# Output_schematic.net
KiCad netlist of a schematic drawn in Altium Designer
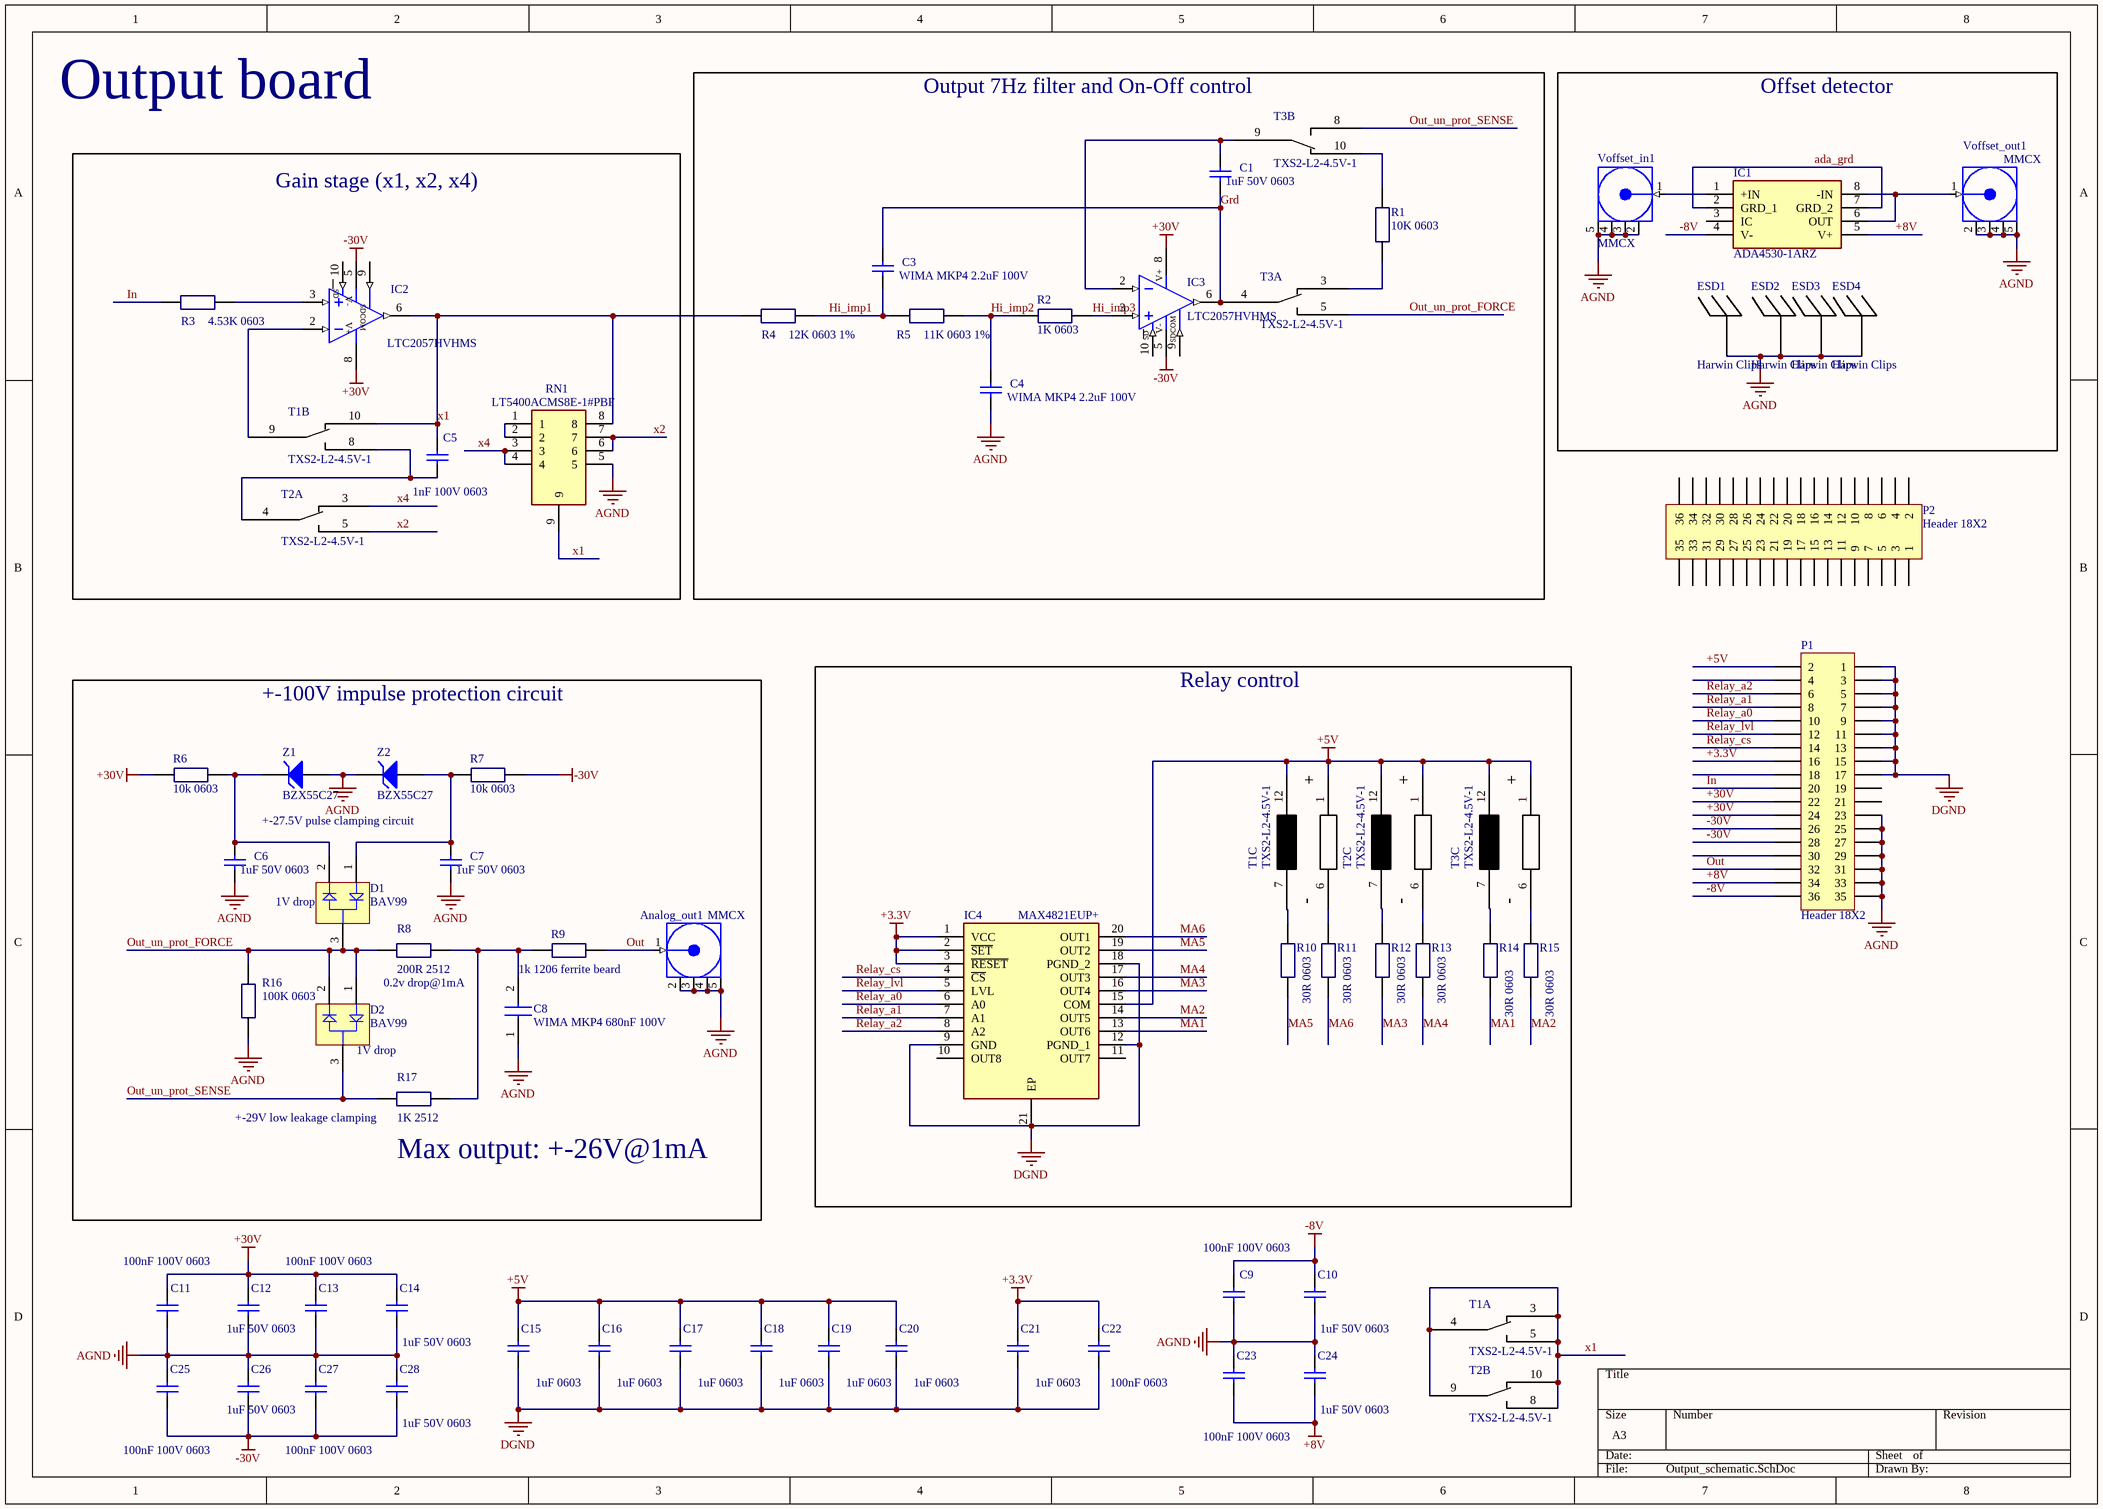
[diagram p0: Output_schematic.SchDoc]

(export (version "E")
  (design (tool "Eeschema 10.0.6"))
  (components
    (comp (ref "Analog_out1")
      (value "MMCX")
      (footprint "MMCX2.54-V5")
      (description "RF Coaxial PCB Connector, MMCX; Thru-Hole, Vertical Mount Plug,  50 Ohm Impedance")
      (fields (field (name "PUBLISHER") "Altium Limited"))
      (libsource (lib "Miscellaneous Connectors") (part "COAX-M"))
    )
    (comp (ref "C1")
      (value "1uF 50V 0603")
      (footprint "CAP 0603")
      (description "Non-polarised capacitor")
      (fields
        (field (name "PART NUMBER") "CC1206_1UF_25V_10%_X7R")
        (field (name "VOLTAGE") "25V")
        (field (name "AUTHOR") "CERN DEM JLC")
      )
      (libsource (lib "Capacitors") (part "Capacitor - non polarized"))
    )
    (comp (ref "C3")
      (value "WIMA MKP4 2.2uF 100V")
      (footprint "90g WIMA MKP4 2.2uF 100V")
      (description "Non-polarised capacitor")
      (fields
        (field (name "PART NUMBER") "CC1206_1UF_25V_10%_X7R")
        (field (name "VOLTAGE") "25V")
        (field (name "AUTHOR") "CERN DEM JLC")
      )
      (libsource (lib "Capacitors") (part "Capacitor - non polarized"))
    )
    (comp (ref "C4")
      (value "WIMA MKP4 2.2uF 100V")
      (footprint "90g WIMA MKP4 2.2uF 100V")
      (description "Non-polarised capacitor")
      (fields
        (field (name "PART NUMBER") "CC1206_1UF_25V_10%_X7R")
        (field (name "VOLTAGE") "25V")
        (field (name "AUTHOR") "CERN DEM JLC")
      )
      (libsource (lib "Capacitors") (part "Capacitor - non polarized"))
    )
    (comp (ref "C5")
      (value "1nF 100V 0603")
      (footprint "CAP 0603")
      (description "Non-polarised capacitor")
      (fields
        (field (name "PART NUMBER") "CC1206_1UF_25V_10%_X7R")
        (field (name "VOLTAGE") "25V")
        (field (name "AUTHOR") "CERN DEM JLC")
      )
      (libsource (lib "Capacitors") (part "Capacitor - non polarized"))
    )
    (comp (ref "C6")
      (value "1uF 50V 0603")
      (footprint "CAP 0603")
      (description "Non-polarised capacitor")
      (fields
        (field (name "PART NUMBER") "CC1206_1UF_25V_10%_X7R")
        (field (name "VOLTAGE") "25V")
        (field (name "AUTHOR") "CERN DEM JLC")
      )
      (libsource (lib "Capacitors") (part "Capacitor - non polarized"))
    )
    (comp (ref "C7")
      (value "1uF 50V 0603")
      (footprint "CAP 0603")
      (description "Non-polarised capacitor")
      (fields
        (field (name "PART NUMBER") "CC1206_1UF_25V_10%_X7R")
        (field (name "VOLTAGE") "25V")
        (field (name "AUTHOR") "CERN DEM JLC")
      )
      (libsource (lib "Capacitors") (part "Capacitor - non polarized"))
    )
    (comp (ref "C8")
      (value "WIMA MKP4 680nF 100V")
      (footprint "SamacSys:MKP4F036804F00KSSD")
      (description "Capacitor")
      (fields
        (field (name "MANUFACTURER_PART_NUMBER") "MKP4F036804F00KSSD")
        (field (name "MOUSER PART NUMBER") "505-MKP4F036804F00KS")
      )
      (libsource (lib "SamacSys") (part "MKP4F036804F00KSSD"))
    )
    (comp (ref "C9")
      (value "100nF 100V 0603")
      (footprint "CAP 0603")
      (description "Non-polarised capacitor")
      (fields
        (field (name "PART NUMBER") "CC1206_1UF_25V_10%_X7R")
        (field (name "VOLTAGE") "25V")
        (field (name "AUTHOR") "CERN DEM JLC")
      )
      (libsource (lib "Capacitors") (part "Capacitor - non polarized"))
    )
    (comp (ref "C10")
      (value "1uF 50V 0603")
      (footprint "CAP 0603")
      (description "Non-polarised capacitor")
      (fields
        (field (name "PART NUMBER") "CC1206_1UF_25V_10%_X7R")
        (field (name "VOLTAGE") "25V")
        (field (name "AUTHOR") "CERN DEM JLC")
      )
      (libsource (lib "Capacitors") (part "Capacitor - non polarized"))
    )
    (comp (ref "C11")
      (value "100nF 100V 0603")
      (footprint "CAP 0603")
      (description "Non-polarised capacitor")
      (fields
        (field (name "PART NUMBER") "CC1206_1UF_25V_10%_X7R")
        (field (name "VOLTAGE") "25V")
        (field (name "AUTHOR") "CERN DEM JLC")
      )
      (libsource (lib "Capacitors") (part "Capacitor - non polarized"))
    )
    (comp (ref "C12")
      (value "1uF 50V 0603")
      (footprint "CAP 0603")
      (description "Non-polarised capacitor")
      (fields
        (field (name "PART NUMBER") "CC1206_1UF_25V_10%_X7R")
        (field (name "VOLTAGE") "25V")
        (field (name "AUTHOR") "CERN DEM JLC")
      )
      (libsource (lib "Capacitors") (part "Capacitor - non polarized"))
    )
    (comp (ref "C13")
      (value "100nF 100V 0603")
      (footprint "CAP 0603")
      (description "Non-polarised capacitor")
      (fields
        (field (name "PART NUMBER") "CC1206_1UF_25V_10%_X7R")
        (field (name "VOLTAGE") "25V")
        (field (name "AUTHOR") "CERN DEM JLC")
      )
      (libsource (lib "Capacitors") (part "Capacitor - non polarized"))
    )
    (comp (ref "C14")
      (value "1uF 50V 0603")
      (footprint "CAP 0603")
      (description "Non-polarised capacitor")
      (fields
        (field (name "PART NUMBER") "CC1206_1UF_25V_10%_X7R")
        (field (name "VOLTAGE") "25V")
        (field (name "AUTHOR") "CERN DEM JLC")
      )
      (libsource (lib "Capacitors") (part "Capacitor - non polarized"))
    )
    (comp (ref "C15")
      (value "1uF 0603")
      (footprint "CAP 0603")
      (description "Non-polarised capacitor")
      (fields
        (field (name "PART NUMBER") "CC1206_1UF_25V_10%_X7R")
        (field (name "VOLTAGE") "25V")
        (field (name "AUTHOR") "CERN DEM JLC")
      )
      (libsource (lib "Capacitors") (part "Capacitor - non polarized"))
    )
    (comp (ref "C16")
      (value "1uF 0603")
      (footprint "CAP 0603")
      (description "Non-polarised capacitor")
      (fields
        (field (name "PART NUMBER") "CC1206_1UF_25V_10%_X7R")
        (field (name "VOLTAGE") "25V")
        (field (name "AUTHOR") "CERN DEM JLC")
      )
      (libsource (lib "Capacitors") (part "Capacitor - non polarized"))
    )
    (comp (ref "C17")
      (value "1uF 0603")
      (footprint "CAP 0603")
      (description "Non-polarised capacitor")
      (fields
        (field (name "PART NUMBER") "CC1206_1UF_25V_10%_X7R")
        (field (name "VOLTAGE") "25V")
        (field (name "AUTHOR") "CERN DEM JLC")
      )
      (libsource (lib "Capacitors") (part "Capacitor - non polarized"))
    )
    (comp (ref "C18")
      (value "1uF 0603")
      (footprint "CAP 0603")
      (description "Non-polarised capacitor")
      (fields
        (field (name "PART NUMBER") "CC1206_1UF_25V_10%_X7R")
        (field (name "VOLTAGE") "25V")
        (field (name "AUTHOR") "CERN DEM JLC")
      )
      (libsource (lib "Capacitors") (part "Capacitor - non polarized"))
    )
    (comp (ref "C19")
      (value "1uF 0603")
      (footprint "CAP 0603")
      (description "Non-polarised capacitor")
      (fields
        (field (name "PART NUMBER") "CC1206_1UF_25V_10%_X7R")
        (field (name "VOLTAGE") "25V")
        (field (name "AUTHOR") "CERN DEM JLC")
      )
      (libsource (lib "Capacitors") (part "Capacitor - non polarized"))
    )
    (comp (ref "C20")
      (value "1uF 0603")
      (footprint "CAP 0603")
      (description "Non-polarised capacitor")
      (fields
        (field (name "PART NUMBER") "CC1206_1UF_25V_10%_X7R")
        (field (name "VOLTAGE") "25V")
        (field (name "AUTHOR") "CERN DEM JLC")
      )
      (libsource (lib "Capacitors") (part "Capacitor - non polarized"))
    )
    (comp (ref "C21")
      (value "1uF 0603")
      (footprint "CAP 0603")
      (description "Non-polarised capacitor")
      (fields
        (field (name "PART NUMBER") "CC1206_1UF_25V_10%_X7R")
        (field (name "VOLTAGE") "25V")
        (field (name "AUTHOR") "CERN DEM JLC")
      )
      (libsource (lib "Capacitors") (part "Capacitor - non polarized"))
    )
    (comp (ref "C22")
      (value "100nF 0603")
      (footprint "CAP 0603")
      (description "Non-polarised capacitor")
      (fields
        (field (name "PART NUMBER") "CC1206_1UF_25V_10%_X7R")
        (field (name "VOLTAGE") "25V")
        (field (name "AUTHOR") "CERN DEM JLC")
      )
      (libsource (lib "Capacitors") (part "Capacitor - non polarized"))
    )
    (comp (ref "C23")
      (value "100nF 100V 0603")
      (footprint "CAP 0603")
      (description "Non-polarised capacitor")
      (fields
        (field (name "PART NUMBER") "CC1206_1UF_25V_10%_X7R")
        (field (name "VOLTAGE") "25V")
        (field (name "AUTHOR") "CERN DEM JLC")
      )
      (libsource (lib "Capacitors") (part "Capacitor - non polarized"))
    )
    (comp (ref "C24")
      (value "1uF 50V 0603")
      (footprint "CAP 0603")
      (description "Non-polarised capacitor")
      (fields
        (field (name "PART NUMBER") "CC1206_1UF_25V_10%_X7R")
        (field (name "VOLTAGE") "25V")
        (field (name "AUTHOR") "CERN DEM JLC")
      )
      (libsource (lib "Capacitors") (part "Capacitor - non polarized"))
    )
    (comp (ref "C25")
      (value "100nF 100V 0603")
      (footprint "CAP 0603")
      (description "Non-polarised capacitor")
      (fields
        (field (name "PART NUMBER") "CC1206_1UF_25V_10%_X7R")
        (field (name "VOLTAGE") "25V")
        (field (name "AUTHOR") "CERN DEM JLC")
      )
      (libsource (lib "Capacitors") (part "Capacitor - non polarized"))
    )
    (comp (ref "C26")
      (value "1uF 50V 0603")
      (footprint "CAP 0603")
      (description "Non-polarised capacitor")
      (fields
        (field (name "PART NUMBER") "CC1206_1UF_25V_10%_X7R")
        (field (name "VOLTAGE") "25V")
        (field (name "AUTHOR") "CERN DEM JLC")
      )
      (libsource (lib "Capacitors") (part "Capacitor - non polarized"))
    )
    (comp (ref "C27")
      (value "100nF 100V 0603")
      (footprint "CAP 0603")
      (description "Non-polarised capacitor")
      (fields
        (field (name "PART NUMBER") "CC1206_1UF_25V_10%_X7R")
        (field (name "VOLTAGE") "25V")
        (field (name "AUTHOR") "CERN DEM JLC")
      )
      (libsource (lib "Capacitors") (part "Capacitor - non polarized"))
    )
    (comp (ref "C28")
      (value "1uF 50V 0603")
      (footprint "CAP 0603")
      (description "Non-polarised capacitor")
      (fields
        (field (name "PART NUMBER") "CC1206_1UF_25V_10%_X7R")
        (field (name "VOLTAGE") "25V")
        (field (name "AUTHOR") "CERN DEM JLC")
      )
      (libsource (lib "Capacitors") (part "Capacitor - non polarized"))
    )
    (comp (ref "D1")
      (value "BAV99")
      (footprint "INF-SOT23_N")
      (description "Silicon Switching Diode, SOT23, Reel, Green")
      (fields (field (name "MANUFACTURER") "Infineon"))
      (libsource (lib "Infineon_Transistor_&_Diode") (part "BAV99"))
    )
    (comp (ref "D2")
      (value "BAV99")
      (footprint "INF-SOT23_N")
      (description "Silicon Switching Diode, SOT23, Reel, Green")
      (fields (field (name "MANUFACTURER") "Infineon"))
      (libsource (lib "Infineon_Transistor_&_Diode") (part "BAV99"))
    )
    (comp (ref "ESD1")
      (value "Harwin Clips")
      (footprint "HARWIN - S0981-46R - CLIP")
      (libsource (lib "My SCH library") (part "Harwin Clips"))
    )
    (comp (ref "ESD2")
      (value "Harwin Clips")
      (footprint "HARWIN - S0981-46R - CLIP")
      (libsource (lib "My SCH library") (part "Harwin Clips"))
    )
    (comp (ref "ESD3")
      (value "Harwin Clips")
      (footprint "HARWIN - S0981-46R - CLIP")
      (libsource (lib "My SCH library") (part "Harwin Clips"))
    )
    (comp (ref "ESD4")
      (value "Harwin Clips")
      (footprint "HARWIN - S0981-46R - CLIP")
      (libsource (lib "My SCH library") (part "Harwin Clips"))
    )
    (comp (ref "IC1")
      (value "ADA4530-1ARZ")
      (footprint "SamacSys:SOIC127P600X175-8N")
      (description "Integrated Circuit")
      (fields (field (name "MOUSER PART NUMBER") "584-ADA4530-1ARZ"))
      (libsource (lib "*") (part "ADA4530-1ARZ"))
    )
    (comp (ref "IC2")
      (value "LTC2057HVHMS")
      (footprint "LT-MS-10_M")
      (description "High Voltage, Low Noise, Zero-Drift Operational  Amplifier")
      (libsource (lib "Operational Amplifiers") (part "LTC2057xHMS"))
    )
    (comp (ref "IC3")
      (value "LTC2057HVHMS")
      (footprint "LT-MS-10_M")
      (description "High Voltage, Low Noise, Zero-Drift Operational  Amplifier")
      (libsource (lib "Operational Amplifiers") (part "LTC2057xHMS"))
    )
    (comp (ref "IC4")
      (value "MAX4821EUP+")
      (footprint "SamacSys:SOP65P638X110-21N")
      (description "Integrated Circuit")
      (fields (field (name "MOUSER PART NUMBER") "700-MAX4821EUP"))
      (libsource (lib "*") (part "MAX4821EUP+"))
    )
    (comp (ref "P1")
      (value "Header 18X2")
      (footprint "HDR2X18")
      (description "Header, 18-Pin, Dual row")
      (fields (field (name "PUBLISHER") "Altium Limited"))
      (libsource (lib "Miscellaneous Connectors") (part "Header 18X2"))
    )
    (comp (ref "P2")
      (value "Header 18X2")
      (footprint "HDR2X18")
      (description "Header, 18-Pin, Dual row")
      (fields (field (name "PUBLISHER") "Altium Limited"))
      (libsource (lib "") (part "Header 18X2_1"))
    )
    (comp (ref "R1")
      (value "10K 0603")
      (footprint "1608[0603]")
      (libsource (lib "Микрон-3") (part "Resistor 0805"))
    )
    (comp (ref "R2")
      (value "1K 0603")
      (footprint "1608[0603]")
      (libsource (lib "Микрон-3") (part "Resistor 0805"))
    )
    (comp (ref "R3")
      (value "4.53K 0603")
      (footprint "1608[0603]")
      (libsource (lib "Микрон-3") (part "Resistor 0805"))
    )
    (comp (ref "R4")
      (value "12K 0603 1%")
      (footprint "1608[0603]")
      (libsource (lib "Микрон-3") (part "Resistor 0805"))
    )
    (comp (ref "R5")
      (value "11K 0603 1%")
      (footprint "1608[0603]")
      (libsource (lib "Микрон-3") (part "Resistor 0805"))
    )
    (comp (ref "R6")
      (value "10k 0603")
      (footprint "1608[0603]")
      (libsource (lib "Микрон-3") (part "Resistor 0805"))
    )
    (comp (ref "R7")
      (value "10k 0603")
      (footprint "1608[0603]")
      (libsource (lib "Микрон-3") (part "Resistor 0805"))
    )
    (comp (ref "R8")
      (value "200R 2512")
      (footprint "CRCW2512")
      (libsource (lib "Микрон-3") (part "Resistor 0805"))
    )
    (comp (ref "R9")
      (value "1k 1206 ferrite beard")
      (footprint "Yageo HV 1206")
      (libsource (lib "Микрон-3") (part "Resistor 0805"))
    )
    (comp (ref "R10")
      (value "30R 0603")
      (footprint "1608[0603]")
      (libsource (lib "Микрон-3") (part "Resistor 0805"))
    )
    (comp (ref "R11")
      (value "30R 0603")
      (footprint "1608[0603]")
      (libsource (lib "Микрон-3") (part "Resistor 0805"))
    )
    (comp (ref "R12")
      (value "30R 0603")
      (footprint "1608[0603]")
      (libsource (lib "Микрон-3") (part "Resistor 0805"))
    )
    (comp (ref "R13")
      (value "30R 0603")
      (footprint "1608[0603]")
      (libsource (lib "Микрон-3") (part "Resistor 0805"))
    )
    (comp (ref "R14")
      (value "30R 0603")
      (footprint "1608[0603]")
      (libsource (lib "Микрон-3") (part "Resistor 0805"))
    )
    (comp (ref "R15")
      (value "30R 0603")
      (footprint "1608[0603]")
      (libsource (lib "Микрон-3") (part "Resistor 0805"))
    )
    (comp (ref "R16")
      (value "100K 0603")
      (footprint "1608[0603]_RES")
      (libsource (lib "Микрон-3") (part "Resistor 0805"))
    )
    (comp (ref "R17")
      (value "1K 2512")
      (footprint "CRCW2512")
      (libsource (lib "Микрон-3") (part "Resistor 0805"))
    )
    (comp (ref "RN1")
      (value "LT5400ACMS8E-1#PBF")
      (footprint "SamacSys:SOP65P490X110-9N")
      (description "Resistor Network")
      (fields (field (name "MOUSER PART NUMBER") "584-5400ACMS8E-1PBF"))
      (libsource (lib "*") (part "LT5400ACMS8E-1#PBF"))
    )
    (comp (ref "T1")
      (value "TXS2-L2-4.5V-1")
      (footprint "TXS2-L2-4.5V-1")
      (libsource (lib "") (part "TXS2-L2-4.5V-1_1"))
    )
    (comp (ref "T2")
      (value "TXS2-L2-4.5V-1")
      (footprint "TXS2-L2-4.5V-1")
      (libsource (lib "My SCH library") (part "TXS2-L2-4.5V-1"))
    )
    (comp (ref "T3")
      (value "TXS2-L2-4.5V-1")
      (footprint "TXS2-L2-4.5V-1")
      (libsource (lib "") (part "TXS2-L2-4.5V-1_1"))
    )
    (comp (ref "Voffset_in1")
      (value "MMCX")
      (footprint "MMCX2.54-V5")
      (description "RF Coaxial PCB Connector, MMCX; Thru-Hole, Vertical Mount Plug,  50 Ohm Impedance")
      (fields (field (name "PUBLISHER") "Altium Limited"))
      (libsource (lib "Miscellaneous Connectors") (part "COAX-M"))
    )
    (comp (ref "Voffset_out1")
      (value "MMCX")
      (footprint "MMCX2.54-V5")
      (description "RF Coaxial PCB Connector, MMCX; Thru-Hole, Vertical Mount Plug,  50 Ohm Impedance")
      (fields (field (name "PUBLISHER") "Altium Limited"))
      (libsource (lib "Miscellaneous Connectors") (part "COAX-M"))
    )
    (comp (ref "Z1")
      (value "BZX55C27")
      (footprint "DO-35")
      (description "Silicon Epitaxial Planar Zener Diode (0.3 to 0.5W)")
      (fields (field (name "PUBLISHER") "Altium Limited"))
      (libsource (lib "Vishay Telefunken Discrete Diode") (part "BZX55C27"))
    )
    (comp (ref "Z2")
      (value "BZX55C27")
      (footprint "DO-35")
      (description "Silicon Epitaxial Planar Zener Diode (0.3 to 0.5W)")
      (fields (field (name "PUBLISHER") "Altium Limited"))
      (libsource (lib "Vishay Telefunken Discrete Diode") (part "BZX55C27"))
    )
  )
  (nets
    (net (code "1") (name "+3.3V") (class "Default")
      (node (ref "C21") (pin "1") (pinfunction "1_1") (pintype "passive"))
      (node (ref "C22") (pin "1") (pinfunction "1_1") (pintype "passive"))
      (node (ref "IC4") (pin "1") (pinfunction "VCC_1") (pintype "passive"))
      (node (ref "IC4") (pin "2") (pinfunction "~{SET}_2") (pintype "passive"))
      (node (ref "IC4") (pin "3") (pinfunction "~{RESET}_3") (pintype "passive"))
      (node (ref "P1") (pin "16") (pinfunction "16_16") (pintype "passive"))
    )
    (net (code "2") (name "+5V") (class "Default")
      (node (ref "C15") (pin "1") (pinfunction "1_1") (pintype "passive"))
      (node (ref "C16") (pin "1") (pinfunction "1_1") (pintype "passive"))
      (node (ref "C17") (pin "1") (pinfunction "1_1") (pintype "passive"))
      (node (ref "C18") (pin "1") (pinfunction "1_1") (pintype "passive"))
      (node (ref "C19") (pin "1") (pinfunction "1_1") (pintype "passive"))
      (node (ref "C20") (pin "1") (pinfunction "1_1") (pintype "passive"))
      (node (ref "IC4") (pin "15") (pinfunction "COM_15") (pintype "passive"))
      (node (ref "P1") (pin "2") (pinfunction "2_2") (pintype "passive"))
      (node (ref "T1") (pin "1") (pinfunction "1_1") (pintype "passive"))
      (node (ref "T1") (pin "12") (pinfunction "12_12") (pintype "passive"))
      (node (ref "T2") (pin "1") (pinfunction "1_1") (pintype "passive"))
      (node (ref "T2") (pin "12") (pinfunction "12_12") (pintype "passive"))
      (node (ref "T3") (pin "1") (pinfunction "1_1") (pintype "passive"))
      (node (ref "T3") (pin "12") (pinfunction "12_12") (pintype "passive"))
    )
    (net (code "3") (name "+8V") (class "Default")
      (node (ref "C23") (pin "2") (pinfunction "2_2") (pintype "passive"))
      (node (ref "C24") (pin "2") (pinfunction "2_2") (pintype "passive"))
      (node (ref "IC1") (pin "5") (pinfunction "V+_5") (pintype "passive"))
      (node (ref "P1") (pin "34") (pinfunction "34_34") (pintype "passive"))
    )
    (net (code "4") (name "+30V") (class "Default")
      (node (ref "C11") (pin "1") (pinfunction "1_1") (pintype "passive"))
      (node (ref "C12") (pin "1") (pinfunction "1_1") (pintype "passive"))
      (node (ref "C13") (pin "1") (pinfunction "1_1") (pintype "passive"))
      (node (ref "C14") (pin "1") (pinfunction "1_1") (pintype "passive"))
      (node (ref "IC2") (pin "8") (pinfunction "V+_8") (pintype "power_in"))
      (node (ref "IC3") (pin "8") (pinfunction "V+_8") (pintype "power_in"))
      (node (ref "P1") (pin "22") (pinfunction "22_22") (pintype "passive"))
      (node (ref "P1") (pin "24") (pinfunction "24_24") (pintype "passive"))
      (node (ref "R6") (pin "1") (pinfunction "A_1") (pintype "passive"))
    )
    (net (code "5") (name "-8V") (class "Default")
      (node (ref "C10") (pin "1") (pinfunction "1_1") (pintype "passive"))
      (node (ref "C9") (pin "1") (pinfunction "1_1") (pintype "passive"))
      (node (ref "IC1") (pin "4") (pinfunction "V-_4") (pintype "passive"))
      (node (ref "P1") (pin "36") (pinfunction "36_36") (pintype "passive"))
    )
    (net (code "6") (name "-30V") (class "Default")
      (node (ref "C25") (pin "2") (pinfunction "2_2") (pintype "passive"))
      (node (ref "C26") (pin "2") (pinfunction "2_2") (pintype "passive"))
      (node (ref "C27") (pin "2") (pinfunction "2_2") (pintype "passive"))
      (node (ref "C28") (pin "2") (pinfunction "2_2") (pintype "passive"))
      (node (ref "IC2") (pin "5") (pinfunction "V-_5") (pintype "power_in"))
      (node (ref "IC3") (pin "5") (pinfunction "V-_5") (pintype "power_in"))
      (node (ref "P1") (pin "26") (pinfunction "26_26") (pintype "passive"))
      (node (ref "P1") (pin "28") (pinfunction "28_28") (pintype "passive"))
      (node (ref "R7") (pin "2") (pinfunction "2_2") (pintype "passive"))
    )
    (net (code "7") (name "/Grd") (class "Default")
      (node (ref "C1") (pin "2") (pinfunction "2_2") (pintype "passive"))
      (node (ref "C3") (pin "1") (pinfunction "1_1") (pintype "passive"))
      (node (ref "IC3") (pin "6") (pinfunction "OUT_6") (pintype "output"))
      (node (ref "T3") (pin "4") (pinfunction "4_4") (pintype "passive"))
    )
    (net (code "8") (name "/Hi_imp1") (class "Default")
      (node (ref "C3") (pin "2") (pinfunction "2_2") (pintype "passive"))
      (node (ref "R4") (pin "1") (pinfunction "A_1") (pintype "passive"))
      (node (ref "R5") (pin "2") (pinfunction "2_2") (pintype "passive"))
    )
    (net (code "9") (name "/Hi_imp2") (class "Default")
      (node (ref "C4") (pin "1") (pinfunction "1_1") (pintype "passive"))
      (node (ref "R2") (pin "1") (pinfunction "A_1") (pintype "passive"))
      (node (ref "R5") (pin "1") (pinfunction "A_1") (pintype "passive"))
    )
    (net (code "10") (name "/Hi_imp3") (class "Default")
      (node (ref "IC3") (pin "3") (pinfunction "IN+_3") (pintype "input"))
      (node (ref "R2") (pin "2") (pinfunction "2_2") (pintype "passive"))
    )
    (net (code "11") (name "/In") (class "Default")
      (node (ref "P1") (pin "20") (pinfunction "20_20") (pintype "passive"))
      (node (ref "R3") (pin "2") (pinfunction "2_2") (pintype "passive"))
    )
    (net (code "12") (name "/MA1") (class "Default")
      (node (ref "IC4") (pin "13") (pinfunction "OUT6_13") (pintype "passive"))
      (node (ref "R14") (pin "2") (pinfunction "2_2") (pintype "passive"))
    )
    (net (code "13") (name "/MA2") (class "Default")
      (node (ref "IC4") (pin "14") (pinfunction "OUT5_14") (pintype "passive"))
      (node (ref "R15") (pin "2") (pinfunction "2_2") (pintype "passive"))
    )
    (net (code "14") (name "/MA3") (class "Default")
      (node (ref "IC4") (pin "16") (pinfunction "OUT4_16") (pintype "passive"))
      (node (ref "R12") (pin "2") (pinfunction "2_2") (pintype "passive"))
    )
    (net (code "15") (name "/MA4") (class "Default")
      (node (ref "IC4") (pin "17") (pinfunction "OUT3_17") (pintype "passive"))
      (node (ref "R13") (pin "2") (pinfunction "2_2") (pintype "passive"))
    )
    (net (code "16") (name "/MA5") (class "Default")
      (node (ref "IC4") (pin "19") (pinfunction "OUT2_19") (pintype "passive"))
      (node (ref "R10") (pin "2") (pinfunction "2_2") (pintype "passive"))
    )
    (net (code "17") (name "/MA6") (class "Default")
      (node (ref "IC4") (pin "20") (pinfunction "OUT1_20") (pintype "passive"))
      (node (ref "R11") (pin "2") (pinfunction "2_2") (pintype "passive"))
    )
    (net (code "18") (name "/Out") (class "Default")
      (node (ref "Analog_out1") (pin "1") (pinfunction "Signal_1") (pintype "input"))
      (node (ref "P1") (pin "32") (pinfunction "32_32") (pintype "passive"))
      (node (ref "R9") (pin "2") (pinfunction "2_2") (pintype "passive"))
    )
    (net (code "19") (name "/Out_un_prot_FORCE") (class "Default")
      (node (ref "D1") (pin "3") (pinfunction "C_3") (pintype "passive"))
      (node (ref "D2") (pin "1") (pinfunction "A1_1") (pintype "passive"))
      (node (ref "D2") (pin "2") (pinfunction "K2_2") (pintype "passive"))
      (node (ref "R16") (pin "1") (pinfunction "A_1") (pintype "passive"))
      (node (ref "R8") (pin "2") (pinfunction "2_2") (pintype "passive"))
      (node (ref "T3") (pin "5") (pinfunction "5_5") (pintype "passive"))
    )
    (net (code "20") (name "/Out_un_prot_SENSE") (class "Default")
      (node (ref "D2") (pin "3") (pinfunction "C_3") (pintype "passive"))
      (node (ref "R17") (pin "2") (pinfunction "2_2") (pintype "passive"))
      (node (ref "T3") (pin "8") (pinfunction "8_8") (pintype "passive"))
    )
    (net (code "21") (name "/Relay_a0") (class "Default")
      (node (ref "IC4") (pin "6") (pinfunction "A0_6") (pintype "passive"))
      (node (ref "P1") (pin "10") (pinfunction "10_10") (pintype "passive"))
    )
    (net (code "22") (name "/Relay_a1") (class "Default")
      (node (ref "IC4") (pin "7") (pinfunction "A1_7") (pintype "passive"))
      (node (ref "P1") (pin "8") (pinfunction "8_8") (pintype "passive"))
    )
    (net (code "23") (name "/Relay_a2") (class "Default")
      (node (ref "IC4") (pin "8") (pinfunction "A2_8") (pintype "passive"))
      (node (ref "P1") (pin "6") (pinfunction "6_6") (pintype "passive"))
    )
    (net (code "24") (name "/Relay_cs") (class "Default")
      (node (ref "IC4") (pin "4") (pinfunction "~{CS}_4") (pintype "passive"))
      (node (ref "P1") (pin "14") (pinfunction "14_14") (pintype "passive"))
    )
    (net (code "25") (name "/Relay_lvl") (class "Default")
      (node (ref "IC4") (pin "5") (pinfunction "LVL_5") (pintype "passive"))
      (node (ref "P1") (pin "12") (pinfunction "12_12") (pintype "passive"))
    )
    (net (code "26") (name "/ada_grd") (class "Default")
      (node (ref "IC1") (pin "2") (pinfunction "GRD_1_2") (pintype "passive"))
      (node (ref "IC1") (pin "7") (pinfunction "GRD_2_7") (pintype "passive"))
    )
    (net (code "27") (name "/x1") (class "Default")
      (node (ref "C5") (pin "1") (pinfunction "1_1") (pintype "passive"))
      (node (ref "IC2") (pin "6") (pinfunction "OUT_6") (pintype "output"))
      (node (ref "R4") (pin "2") (pinfunction "2_2") (pintype "passive"))
      (node (ref "RN1") (pin "8") (pinfunction "8_8") (pintype "passive"))
      (node (ref "RN1") (pin "9") (pinfunction "9_9") (pintype "passive"))
      (node (ref "T1") (pin "10") (pinfunction "10_10") (pintype "passive"))
      (node (ref "T1") (pin "3") (pinfunction "3_3") (pintype "passive"))
      (node (ref "T1") (pin "4") (pinfunction "4_4") (pintype "passive"))
      (node (ref "T1") (pin "5") (pinfunction "5_5") (pintype "passive"))
      (node (ref "T2") (pin "10") (pinfunction "10_10") (pintype "passive"))
      (node (ref "T2") (pin "8") (pinfunction "8_8") (pintype "passive"))
      (node (ref "T2") (pin "9") (pinfunction "9_9") (pintype "passive"))
    )
    (net (code "28") (name "/x2") (class "Default")
      (node (ref "RN1") (pin "6") (pinfunction "6_6") (pintype "passive"))
      (node (ref "RN1") (pin "7") (pinfunction "7_7") (pintype "passive"))
      (node (ref "T2") (pin "5") (pinfunction "5_5") (pintype "passive"))
    )
    (net (code "29") (name "/x4") (class "Default")
      (node (ref "RN1") (pin "3") (pinfunction "3_3") (pintype "passive"))
      (node (ref "RN1") (pin "4") (pinfunction "4_4") (pintype "passive"))
      (node (ref "T2") (pin "3") (pinfunction "3_3") (pintype "passive"))
    )
    (net (code "30") (name "AGND") (class "Default")
      (node (ref "Analog_out1") (pin "2") (pinfunction "GND_2") (pintype "power_in"))
      (node (ref "Analog_out1") (pin "3") (pinfunction "GND_3") (pintype "power_in"))
      (node (ref "Analog_out1") (pin "4") (pinfunction "GND_4") (pintype "power_in"))
      (node (ref "Analog_out1") (pin "5") (pinfunction "GND_5") (pintype "power_in"))
      (node (ref "C10") (pin "2") (pinfunction "2_2") (pintype "passive"))
      (node (ref "C11") (pin "2") (pinfunction "2_2") (pintype "passive"))
      (node (ref "C12") (pin "2") (pinfunction "2_2") (pintype "passive"))
      (node (ref "C13") (pin "2") (pinfunction "2_2") (pintype "passive"))
      (node (ref "C14") (pin "2") (pinfunction "2_2") (pintype "passive"))
      (node (ref "C23") (pin "1") (pinfunction "1_1") (pintype "passive"))
      (node (ref "C24") (pin "1") (pinfunction "1_1") (pintype "passive"))
      (node (ref "C25") (pin "1") (pinfunction "1_1") (pintype "passive"))
      (node (ref "C26") (pin "1") (pinfunction "1_1") (pintype "passive"))
      (node (ref "C27") (pin "1") (pinfunction "1_1") (pintype "passive"))
      (node (ref "C28") (pin "1") (pinfunction "1_1") (pintype "passive"))
      (node (ref "C4") (pin "2") (pinfunction "2_2") (pintype "passive"))
      (node (ref "C6") (pin "2") (pinfunction "2_2") (pintype "passive"))
      (node (ref "C7") (pin "2") (pinfunction "2_2") (pintype "passive"))
      (node (ref "C8") (pin "1") (pinfunction "1_1") (pintype "passive"))
      (node (ref "C9") (pin "2") (pinfunction "2_2") (pintype "passive"))
      (node (ref "ESD1") (pin "1") (pinfunction "1_1") (pintype "passive"))
      (node (ref "ESD2") (pin "1") (pinfunction "1_1") (pintype "passive"))
      (node (ref "ESD3") (pin "1") (pinfunction "1_1") (pintype "passive"))
      (node (ref "ESD4") (pin "1") (pinfunction "1_1") (pintype "passive"))
      (node (ref "P1") (pin "23") (pinfunction "23_23") (pintype "passive"))
      (node (ref "P1") (pin "25") (pinfunction "25_25") (pintype "passive"))
      (node (ref "P1") (pin "27") (pinfunction "27_27") (pintype "passive"))
      (node (ref "P1") (pin "29") (pinfunction "29_29") (pintype "passive"))
      (node (ref "P1") (pin "31") (pinfunction "31_31") (pintype "passive"))
      (node (ref "P1") (pin "33") (pinfunction "33_33") (pintype "passive"))
      (node (ref "P1") (pin "35") (pinfunction "35_35") (pintype "passive"))
      (node (ref "R16") (pin "2") (pinfunction "2_2") (pintype "passive"))
      (node (ref "RN1") (pin "5") (pinfunction "5_5") (pintype "passive"))
      (node (ref "Voffset_in1") (pin "2") (pinfunction "GND_2") (pintype "power_in"))
      (node (ref "Voffset_in1") (pin "3") (pinfunction "GND_3") (pintype "power_in"))
      (node (ref "Voffset_in1") (pin "4") (pinfunction "GND_4") (pintype "power_in"))
      (node (ref "Voffset_in1") (pin "5") (pinfunction "GND_5") (pintype "power_in"))
      (node (ref "Voffset_out1") (pin "2") (pinfunction "GND_2") (pintype "power_in"))
      (node (ref "Voffset_out1") (pin "3") (pinfunction "GND_3") (pintype "power_in"))
      (node (ref "Voffset_out1") (pin "4") (pinfunction "GND_4") (pintype "power_in"))
      (node (ref "Voffset_out1") (pin "5") (pinfunction "GND_5") (pintype "power_in"))
      (node (ref "Z1") (pin "1") (pinfunction "A_1") (pintype "passive"))
      (node (ref "Z2") (pin "2") (pinfunction "K_2") (pintype "passive"))
    )
    (net (code "31") (name "DGND") (class "Default")
      (node (ref "C15") (pin "2") (pinfunction "2_2") (pintype "passive"))
      (node (ref "C16") (pin "2") (pinfunction "2_2") (pintype "passive"))
      (node (ref "C17") (pin "2") (pinfunction "2_2") (pintype "passive"))
      (node (ref "C18") (pin "2") (pinfunction "2_2") (pintype "passive"))
      (node (ref "C19") (pin "2") (pinfunction "2_2") (pintype "passive"))
      (node (ref "C20") (pin "2") (pinfunction "2_2") (pintype "passive"))
      (node (ref "C21") (pin "2") (pinfunction "2_2") (pintype "passive"))
      (node (ref "C22") (pin "2") (pinfunction "2_2") (pintype "passive"))
      (node (ref "IC4") (pin "12") (pinfunction "PGND_1_12") (pintype "passive"))
      (node (ref "IC4") (pin "18") (pinfunction "PGND_2_18") (pintype "passive"))
      (node (ref "IC4") (pin "21") (pinfunction "EP_21") (pintype "passive"))
      (node (ref "IC4") (pin "9") (pinfunction "GND_9") (pintype "passive"))
      (node (ref "P1") (pin "1") (pinfunction "1_1") (pintype "passive"))
      (node (ref "P1") (pin "11") (pinfunction "11_11") (pintype "passive"))
      (node (ref "P1") (pin "13") (pinfunction "13_13") (pintype "passive"))
      (node (ref "P1") (pin "15") (pinfunction "15_15") (pintype "passive"))
      (node (ref "P1") (pin "17") (pinfunction "17_17") (pintype "passive"))
      (node (ref "P1") (pin "3") (pinfunction "3_3") (pintype "passive"))
      (node (ref "P1") (pin "5") (pinfunction "5_5") (pintype "passive"))
      (node (ref "P1") (pin "7") (pinfunction "7_7") (pintype "passive"))
      (node (ref "P1") (pin "9") (pinfunction "9_9") (pintype "passive"))
    )
    (net (code "32") (name "Net-(C5-Pad2)") (class "Default")
      (node (ref "C5") (pin "2") (pinfunction "2_2") (pintype "passive"))
      (node (ref "T1") (pin "8") (pinfunction "8_8") (pintype "passive"))
      (node (ref "T2") (pin "4") (pinfunction "4_4") (pintype "passive"))
    )
    (net (code "33") (name "Net-(D1-A1)") (class "Default")
      (node (ref "C7") (pin "1") (pinfunction "1_1") (pintype "passive"))
      (node (ref "D1") (pin "1") (pinfunction "A1_1") (pintype "passive"))
      (node (ref "R7") (pin "1") (pinfunction "A_1") (pintype "passive"))
      (node (ref "Z2") (pin "1") (pinfunction "A_1") (pintype "passive"))
    )
    (net (code "34") (name "Net-(D1-K2)") (class "Default")
      (node (ref "C6") (pin "1") (pinfunction "1_1") (pintype "passive"))
      (node (ref "D1") (pin "2") (pinfunction "K2_2") (pintype "passive"))
      (node (ref "R6") (pin "2") (pinfunction "2_2") (pintype "passive"))
      (node (ref "Z1") (pin "2") (pinfunction "K_2") (pintype "passive"))
    )
    (net (code "35") (name "Net-(IC1-+IN)") (class "Default")
      (node (ref "IC1") (pin "1") (pinfunction "+IN_1") (pintype "passive"))
      (node (ref "Voffset_in1") (pin "1") (pinfunction "Signal_1") (pintype "input"))
    )
    (net (code "36") (name "Net-(IC1--IN)") (class "Default")
      (node (ref "IC1") (pin "6") (pinfunction "OUT_6") (pintype "passive"))
      (node (ref "IC1") (pin "8") (pinfunction "-IN_8") (pintype "passive"))
      (node (ref "Voffset_out1") (pin "1") (pinfunction "Signal_1") (pintype "input"))
    )
    (net (code "37") (name "Net-(IC2-IN+)") (class "Default")
      (node (ref "IC2") (pin "3") (pinfunction "IN+_3") (pintype "input"))
      (node (ref "R3") (pin "1") (pinfunction "A_1") (pintype "passive"))
    )
    (net (code "38") (name "Net-(IC2-IN-)") (class "Default")
      (node (ref "IC2") (pin "2") (pinfunction "IN-_2") (pintype "input"))
      (node (ref "T1") (pin "9") (pinfunction "9_9") (pintype "passive"))
    )
    (net (code "39") (name "Net-(IC3-IN-)") (class "Default")
      (node (ref "C1") (pin "1") (pinfunction "1_1") (pintype "passive"))
      (node (ref "IC3") (pin "2") (pinfunction "IN-_2") (pintype "input"))
      (node (ref "T3") (pin "9") (pinfunction "9_9") (pintype "passive"))
    )
    (net (code "40") (name "Net-(R1-A)") (class "Default")
      (node (ref "R1") (pin "1") (pinfunction "A_1") (pintype "passive"))
      (node (ref "T3") (pin "3") (pinfunction "3_3") (pintype "passive"))
    )
    (net (code "41") (name "Net-(R1-Pad2)") (class "Default")
      (node (ref "R1") (pin "2") (pinfunction "2_2") (pintype "passive"))
      (node (ref "T3") (pin "10") (pinfunction "10_10") (pintype "passive"))
    )
    (net (code "42") (name "Net-(R10-A)") (class "Default")
      (node (ref "R10") (pin "1") (pinfunction "A_1") (pintype "passive"))
      (node (ref "T1") (pin "7") (pinfunction "7_7") (pintype "passive"))
    )
    (net (code "43") (name "Net-(R11-A)") (class "Default")
      (node (ref "R11") (pin "1") (pinfunction "A_1") (pintype "passive"))
      (node (ref "T1") (pin "6") (pinfunction "6_6") (pintype "passive"))
    )
    (net (code "44") (name "Net-(R12-A)") (class "Default")
      (node (ref "R12") (pin "1") (pinfunction "A_1") (pintype "passive"))
      (node (ref "T2") (pin "7") (pinfunction "7_7") (pintype "passive"))
    )
    (net (code "45") (name "Net-(R13-A)") (class "Default")
      (node (ref "R13") (pin "1") (pinfunction "A_1") (pintype "passive"))
      (node (ref "T2") (pin "6") (pinfunction "6_6") (pintype "passive"))
    )
    (net (code "46") (name "Net-(R14-A)") (class "Default")
      (node (ref "R14") (pin "1") (pinfunction "A_1") (pintype "passive"))
      (node (ref "T3") (pin "7") (pinfunction "7_7") (pintype "passive"))
    )
    (net (code "47") (name "Net-(R15-A)") (class "Default")
      (node (ref "R15") (pin "1") (pinfunction "A_1") (pintype "passive"))
      (node (ref "T3") (pin "6") (pinfunction "6_6") (pintype "passive"))
    )
    (net (code "48") (name "Net-(R17-A)") (class "Default")
      (node (ref "C8") (pin "2") (pinfunction "2_2") (pintype "passive"))
      (node (ref "R17") (pin "1") (pinfunction "A_1") (pintype "passive"))
      (node (ref "R8") (pin "1") (pinfunction "A_1") (pintype "passive"))
      (node (ref "R9") (pin "1") (pinfunction "A_1") (pintype "passive"))
    )
    (net (code "49") (name "Net-(RN1-Pad1)") (class "Default")
      (node (ref "RN1") (pin "1") (pinfunction "1_1") (pintype "passive"))
      (node (ref "RN1") (pin "2") (pinfunction "2_2") (pintype "passive"))
    )
    (net (code "50") (name "unconnected-(IC1-IC-Pad3)") (class "Default")
      (node (ref "IC1") (pin "3") (pinfunction "IC_3") (pintype "passive"))
    )
    (net (code "51") (name "unconnected-(IC2-SDCOM-Pad9)") (class "Default")
      (node (ref "IC2") (pin "9") (pinfunction "SDCOM_9") (pintype "input"))
    )
    (net (code "52") (name "unconnected-(IC2-~{SD}-Pad10)") (class "Default")
      (node (ref "IC2") (pin "10") (pinfunction "~{SD}_10") (pintype "input"))
    )
    (net (code "53") (name "unconnected-(IC3-SDCOM-Pad9)") (class "Default")
      (node (ref "IC3") (pin "9") (pinfunction "SDCOM_9") (pintype "input"))
    )
    (net (code "54") (name "unconnected-(IC3-~{SD}-Pad10)") (class "Default")
      (node (ref "IC3") (pin "10") (pinfunction "~{SD}_10") (pintype "input"))
    )
    (net (code "55") (name "unconnected-(IC4-OUT7-Pad11)") (class "Default")
      (node (ref "IC4") (pin "11") (pinfunction "OUT7_11") (pintype "passive"))
    )
    (net (code "56") (name "unconnected-(IC4-OUT8-Pad10)") (class "Default")
      (node (ref "IC4") (pin "10") (pinfunction "OUT8_10") (pintype "passive"))
    )
    (net (code "57") (name "unconnected-(P1-Pad4)") (class "Default")
      (node (ref "P1") (pin "4") (pinfunction "4_4") (pintype "passive"))
    )
    (net (code "58") (name "unconnected-(P1-Pad18)") (class "Default")
      (node (ref "P1") (pin "18") (pinfunction "18_18") (pintype "passive"))
    )
    (net (code "59") (name "unconnected-(P1-Pad19)") (class "Default")
      (node (ref "P1") (pin "19") (pinfunction "19_19") (pintype "passive"))
    )
    (net (code "60") (name "unconnected-(P1-Pad21)") (class "Default")
      (node (ref "P1") (pin "21") (pinfunction "21_21") (pintype "passive"))
    )
    (net (code "61") (name "unconnected-(P1-Pad30)") (class "Default")
      (node (ref "P1") (pin "30") (pinfunction "30_30") (pintype "passive"))
    )
    (net (code "62") (name "unconnected-(P2-Pad1)") (class "Default")
      (node (ref "P2") (pin "1") (pinfunction "1_1") (pintype "passive"))
    )
    (net (code "63") (name "unconnected-(P2-Pad2)") (class "Default")
      (node (ref "P2") (pin "2") (pinfunction "2_2") (pintype "passive"))
    )
    (net (code "64") (name "unconnected-(P2-Pad3)") (class "Default")
      (node (ref "P2") (pin "3") (pinfunction "3_3") (pintype "passive"))
    )
    (net (code "65") (name "unconnected-(P2-Pad4)") (class "Default")
      (node (ref "P2") (pin "4") (pinfunction "4_4") (pintype "passive"))
    )
    (net (code "66") (name "unconnected-(P2-Pad5)") (class "Default")
      (node (ref "P2") (pin "5") (pinfunction "5_5") (pintype "passive"))
    )
    (net (code "67") (name "unconnected-(P2-Pad6)") (class "Default")
      (node (ref "P2") (pin "6") (pinfunction "6_6") (pintype "passive"))
    )
    (net (code "68") (name "unconnected-(P2-Pad7)") (class "Default")
      (node (ref "P2") (pin "7") (pinfunction "7_7") (pintype "passive"))
    )
    (net (code "69") (name "unconnected-(P2-Pad8)") (class "Default")
      (node (ref "P2") (pin "8") (pinfunction "8_8") (pintype "passive"))
    )
    (net (code "70") (name "unconnected-(P2-Pad9)") (class "Default")
      (node (ref "P2") (pin "9") (pinfunction "9_9") (pintype "passive"))
    )
    (net (code "71") (name "unconnected-(P2-Pad10)") (class "Default")
      (node (ref "P2") (pin "10") (pinfunction "10_10") (pintype "passive"))
    )
    (net (code "72") (name "unconnected-(P2-Pad11)") (class "Default")
      (node (ref "P2") (pin "11") (pinfunction "11_11") (pintype "passive"))
    )
    (net (code "73") (name "unconnected-(P2-Pad12)") (class "Default")
      (node (ref "P2") (pin "12") (pinfunction "12_12") (pintype "passive"))
    )
    (net (code "74") (name "unconnected-(P2-Pad13)") (class "Default")
      (node (ref "P2") (pin "13") (pinfunction "13_13") (pintype "passive"))
    )
    (net (code "75") (name "unconnected-(P2-Pad14)") (class "Default")
      (node (ref "P2") (pin "14") (pinfunction "14_14") (pintype "passive"))
    )
    (net (code "76") (name "unconnected-(P2-Pad15)") (class "Default")
      (node (ref "P2") (pin "15") (pinfunction "15_15") (pintype "passive"))
    )
    (net (code "77") (name "unconnected-(P2-Pad16)") (class "Default")
      (node (ref "P2") (pin "16") (pinfunction "16_16") (pintype "passive"))
    )
    (net (code "78") (name "unconnected-(P2-Pad17)") (class "Default")
      (node (ref "P2") (pin "17") (pinfunction "17_17") (pintype "passive"))
    )
    (net (code "79") (name "unconnected-(P2-Pad18)") (class "Default")
      (node (ref "P2") (pin "18") (pinfunction "18_18") (pintype "passive"))
    )
    (net (code "80") (name "unconnected-(P2-Pad19)") (class "Default")
      (node (ref "P2") (pin "19") (pinfunction "19_19") (pintype "passive"))
    )
    (net (code "81") (name "unconnected-(P2-Pad20)") (class "Default")
      (node (ref "P2") (pin "20") (pinfunction "20_20") (pintype "passive"))
    )
    (net (code "82") (name "unconnected-(P2-Pad21)") (class "Default")
      (node (ref "P2") (pin "21") (pinfunction "21_21") (pintype "passive"))
    )
    (net (code "83") (name "unconnected-(P2-Pad22)") (class "Default")
      (node (ref "P2") (pin "22") (pinfunction "22_22") (pintype "passive"))
    )
    (net (code "84") (name "unconnected-(P2-Pad23)") (class "Default")
      (node (ref "P2") (pin "23") (pinfunction "23_23") (pintype "passive"))
    )
    (net (code "85") (name "unconnected-(P2-Pad24)") (class "Default")
      (node (ref "P2") (pin "24") (pinfunction "24_24") (pintype "passive"))
    )
    (net (code "86") (name "unconnected-(P2-Pad25)") (class "Default")
      (node (ref "P2") (pin "25") (pinfunction "25_25") (pintype "passive"))
    )
    (net (code "87") (name "unconnected-(P2-Pad26)") (class "Default")
      (node (ref "P2") (pin "26") (pinfunction "26_26") (pintype "passive"))
    )
    (net (code "88") (name "unconnected-(P2-Pad27)") (class "Default")
      (node (ref "P2") (pin "27") (pinfunction "27_27") (pintype "passive"))
    )
    (net (code "89") (name "unconnected-(P2-Pad28)") (class "Default")
      (node (ref "P2") (pin "28") (pinfunction "28_28") (pintype "passive"))
    )
    (net (code "90") (name "unconnected-(P2-Pad29)") (class "Default")
      (node (ref "P2") (pin "29") (pinfunction "29_29") (pintype "passive"))
    )
    (net (code "91") (name "unconnected-(P2-Pad30)") (class "Default")
      (node (ref "P2") (pin "30") (pinfunction "30_30") (pintype "passive"))
    )
    (net (code "92") (name "unconnected-(P2-Pad31)") (class "Default")
      (node (ref "P2") (pin "31") (pinfunction "31_31") (pintype "passive"))
    )
    (net (code "93") (name "unconnected-(P2-Pad32)") (class "Default")
      (node (ref "P2") (pin "32") (pinfunction "32_32") (pintype "passive"))
    )
    (net (code "94") (name "unconnected-(P2-Pad33)") (class "Default")
      (node (ref "P2") (pin "33") (pinfunction "33_33") (pintype "passive"))
    )
    (net (code "95") (name "unconnected-(P2-Pad34)") (class "Default")
      (node (ref "P2") (pin "34") (pinfunction "34_34") (pintype "passive"))
    )
    (net (code "96") (name "unconnected-(P2-Pad35)") (class "Default")
      (node (ref "P2") (pin "35") (pinfunction "35_35") (pintype "passive"))
    )
    (net (code "97") (name "unconnected-(P2-Pad36)") (class "Default")
      (node (ref "P2") (pin "36") (pinfunction "36_36") (pintype "passive"))
    )
  )
)
